# 7-jack-sensor-board.net
KiCad netlist of a schematic drawn in EAGLE
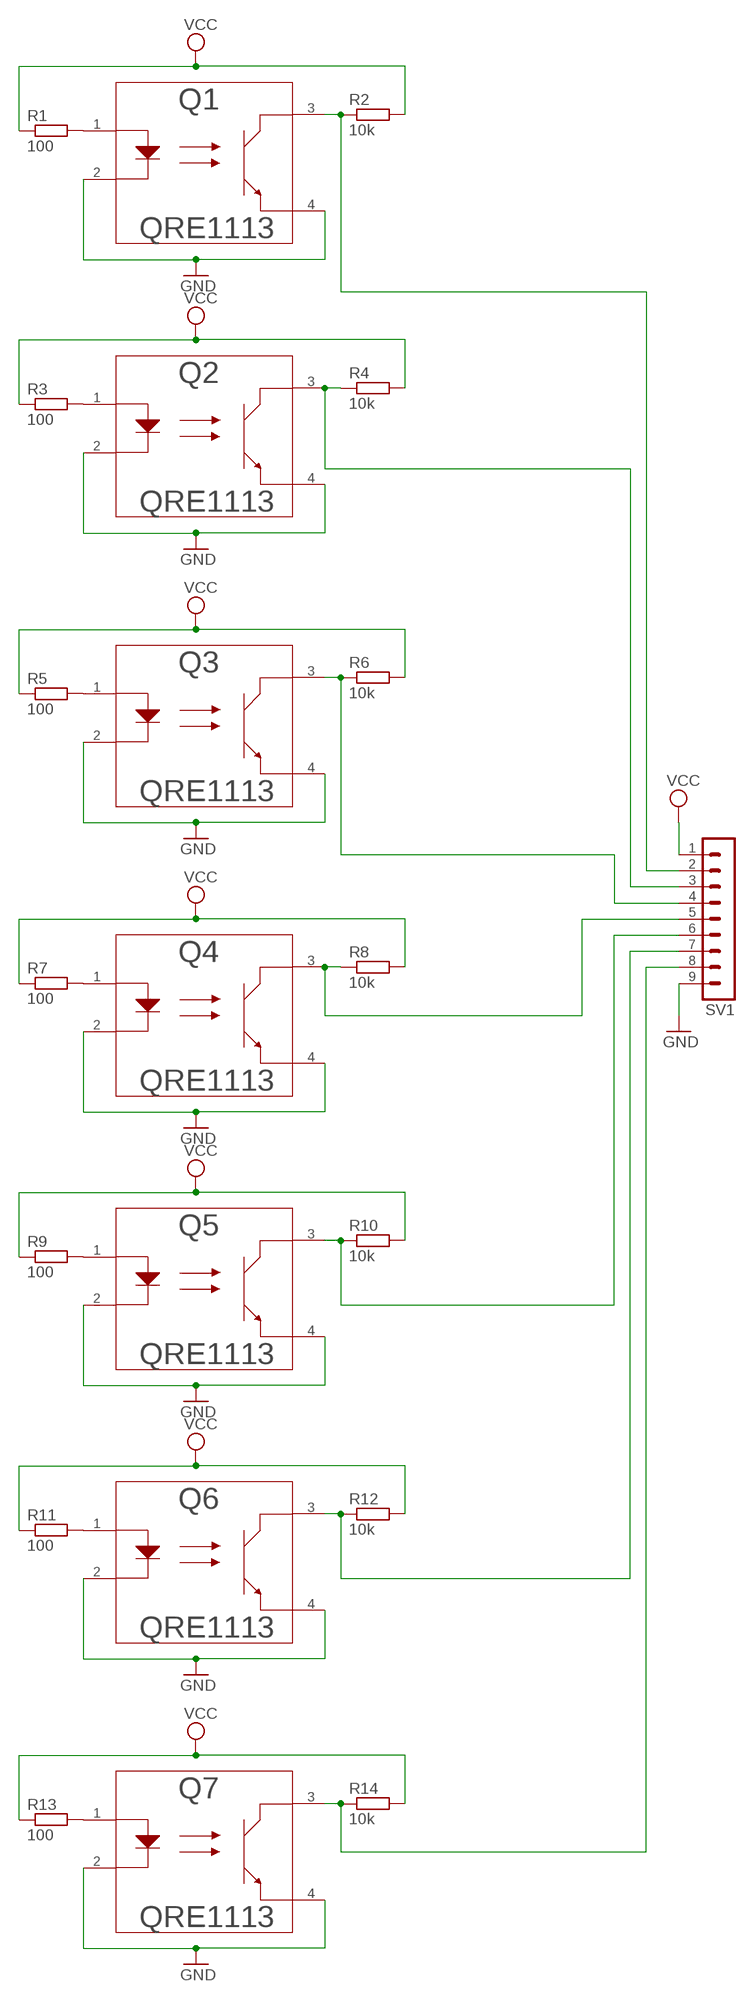
[diagram p0: schematic, sheet 1]

(export (version "E")
  (design (tool "Eeschema 10.0.6"))
  (components
    (comp (ref "Q1")
      (value "QRE1113")
      (footprint "eagle-import:DIP4_100AQ_ONS")
      (fields (field (name "COPYRIGHT") "Copyright (C) 2024 Ultra Librarian. All rights reserved."))
      (libsource (lib "eagle-import") (part "QRE1113"))
    )
    (comp (ref "Q2")
      (value "QRE1113")
      (footprint "eagle-import:DIP4_100AQ_ONS")
      (fields (field (name "COPYRIGHT") "Copyright (C) 2024 Ultra Librarian. All rights reserved."))
      (libsource (lib "eagle-import") (part "QRE1113"))
    )
    (comp (ref "Q3")
      (value "QRE1113")
      (footprint "eagle-import:DIP4_100AQ_ONS")
      (fields (field (name "COPYRIGHT") "Copyright (C) 2024 Ultra Librarian. All rights reserved."))
      (libsource (lib "eagle-import") (part "QRE1113"))
    )
    (comp (ref "Q4")
      (value "QRE1113")
      (footprint "eagle-import:DIP4_100AQ_ONS")
      (fields (field (name "COPYRIGHT") "Copyright (C) 2024 Ultra Librarian. All rights reserved."))
      (libsource (lib "eagle-import") (part "QRE1113"))
    )
    (comp (ref "Q5")
      (value "QRE1113")
      (footprint "eagle-import:DIP4_100AQ_ONS")
      (fields (field (name "COPYRIGHT") "Copyright (C) 2024 Ultra Librarian. All rights reserved."))
      (libsource (lib "eagle-import") (part "QRE1113"))
    )
    (comp (ref "Q6")
      (value "QRE1113")
      (footprint "eagle-import:DIP4_100AQ_ONS")
      (fields (field (name "COPYRIGHT") "Copyright (C) 2024 Ultra Librarian. All rights reserved."))
      (libsource (lib "eagle-import") (part "QRE1113"))
    )
    (comp (ref "Q7")
      (value "QRE1113")
      (footprint "eagle-import:DIP4_100AQ_ONS")
      (fields (field (name "COPYRIGHT") "Copyright (C) 2024 Ultra Librarian. All rights reserved."))
      (libsource (lib "eagle-import") (part "QRE1113"))
    )
    (comp (ref "R1")
      (value "100")
      (footprint "eagle-import:0207_10")
      (libsource (lib "eagle-import") (part "R-EU_0207/10"))
    )
    (comp (ref "R2")
      (value "10k")
      (footprint "eagle-import:0207_10")
      (libsource (lib "eagle-import") (part "R-EU_0207/10"))
    )
    (comp (ref "R3")
      (value "100")
      (footprint "eagle-import:0207_10")
      (libsource (lib "eagle-import") (part "R-EU_0207/10"))
    )
    (comp (ref "R4")
      (value "10k")
      (footprint "eagle-import:0207_10")
      (libsource (lib "eagle-import") (part "R-EU_0207/10"))
    )
    (comp (ref "R5")
      (value "100")
      (footprint "eagle-import:0207_10")
      (libsource (lib "eagle-import") (part "R-EU_0207/10"))
    )
    (comp (ref "R6")
      (value "10k")
      (footprint "eagle-import:0207_10")
      (libsource (lib "eagle-import") (part "R-EU_0207/10"))
    )
    (comp (ref "R7")
      (value "100")
      (footprint "eagle-import:0207_10")
      (libsource (lib "eagle-import") (part "R-EU_0207/10"))
    )
    (comp (ref "R8")
      (value "10k")
      (footprint "eagle-import:0207_10")
      (libsource (lib "eagle-import") (part "R-EU_0207/10"))
    )
    (comp (ref "R9")
      (value "100")
      (footprint "eagle-import:0207_10")
      (libsource (lib "eagle-import") (part "R-EU_0207/10"))
    )
    (comp (ref "R10")
      (value "10k")
      (footprint "eagle-import:0207_10")
      (libsource (lib "eagle-import") (part "R-EU_0207/10"))
    )
    (comp (ref "R11")
      (value "100")
      (footprint "eagle-import:0207_10")
      (libsource (lib "eagle-import") (part "R-EU_0207/10"))
    )
    (comp (ref "R12")
      (value "10k")
      (footprint "eagle-import:0207_10")
      (libsource (lib "eagle-import") (part "R-EU_0207/10"))
    )
    (comp (ref "R13")
      (value "100")
      (footprint "eagle-import:0207_10")
      (libsource (lib "eagle-import") (part "R-EU_0207/10"))
    )
    (comp (ref "R14")
      (value "10k")
      (footprint "eagle-import:0207_10")
      (libsource (lib "eagle-import") (part "R-EU_0207/10"))
    )
    (comp (ref "SV1")
      (value "MA09-1")
      (footprint "eagle-import:MA09-1")
      (libsource (lib "eagle-import") (part "MA09-1"))
    )
  )
  (nets
    (net (code "1") (name "GND") (class "Default")
      (node (ref "Q1") (pin "2") (pinfunction "2_2") (pintype "passive"))
      (node (ref "Q1") (pin "4") (pinfunction "4_4") (pintype "passive"))
      (node (ref "Q2") (pin "2") (pinfunction "2_2") (pintype "passive"))
      (node (ref "Q2") (pin "4") (pinfunction "4_4") (pintype "passive"))
      (node (ref "Q3") (pin "2") (pinfunction "2_2") (pintype "passive"))
      (node (ref "Q3") (pin "4") (pinfunction "4_4") (pintype "passive"))
      (node (ref "Q4") (pin "2") (pinfunction "2_2") (pintype "passive"))
      (node (ref "Q4") (pin "4") (pinfunction "4_4") (pintype "passive"))
      (node (ref "Q5") (pin "2") (pinfunction "2_2") (pintype "passive"))
      (node (ref "Q5") (pin "4") (pinfunction "4_4") (pintype "passive"))
      (node (ref "Q6") (pin "2") (pinfunction "2_2") (pintype "passive"))
      (node (ref "Q6") (pin "4") (pinfunction "4_4") (pintype "passive"))
      (node (ref "Q7") (pin "2") (pinfunction "2_2") (pintype "passive"))
      (node (ref "Q7") (pin "4") (pinfunction "4_4") (pintype "passive"))
      (node (ref "SV1") (pin "9") (pinfunction "9_9") (pintype "passive"))
    )
    (net (code "2") (name "Net-(Q1-Pad1)") (class "Default")
      (node (ref "Q1") (pin "1") (pinfunction "1_1") (pintype "passive"))
      (node (ref "R1") (pin "2") (pinfunction "2_2") (pintype "passive"))
    )
    (net (code "3") (name "Net-(Q1-Pad3)") (class "Default")
      (node (ref "Q1") (pin "3") (pinfunction "3_3") (pintype "passive"))
      (node (ref "R2") (pin "1") (pinfunction "1_1") (pintype "passive"))
      (node (ref "SV1") (pin "2") (pinfunction "2_2") (pintype "passive"))
    )
    (net (code "4") (name "Net-(Q2-Pad1)") (class "Default")
      (node (ref "Q2") (pin "1") (pinfunction "1_1") (pintype "passive"))
      (node (ref "R3") (pin "2") (pinfunction "2_2") (pintype "passive"))
    )
    (net (code "5") (name "Net-(Q2-Pad3)") (class "Default")
      (node (ref "Q2") (pin "3") (pinfunction "3_3") (pintype "passive"))
      (node (ref "R4") (pin "1") (pinfunction "1_1") (pintype "passive"))
      (node (ref "SV1") (pin "3") (pinfunction "3_3") (pintype "passive"))
    )
    (net (code "6") (name "Net-(Q3-Pad1)") (class "Default")
      (node (ref "Q3") (pin "1") (pinfunction "1_1") (pintype "passive"))
      (node (ref "R5") (pin "2") (pinfunction "2_2") (pintype "passive"))
    )
    (net (code "7") (name "Net-(Q3-Pad3)") (class "Default")
      (node (ref "Q3") (pin "3") (pinfunction "3_3") (pintype "passive"))
      (node (ref "R6") (pin "1") (pinfunction "1_1") (pintype "passive"))
      (node (ref "SV1") (pin "4") (pinfunction "4_4") (pintype "passive"))
    )
    (net (code "8") (name "Net-(Q4-Pad1)") (class "Default")
      (node (ref "Q4") (pin "1") (pinfunction "1_1") (pintype "passive"))
      (node (ref "R7") (pin "2") (pinfunction "2_2") (pintype "passive"))
    )
    (net (code "9") (name "Net-(Q4-Pad3)") (class "Default")
      (node (ref "Q4") (pin "3") (pinfunction "3_3") (pintype "passive"))
      (node (ref "R8") (pin "1") (pinfunction "1_1") (pintype "passive"))
      (node (ref "SV1") (pin "5") (pinfunction "5_5") (pintype "passive"))
    )
    (net (code "10") (name "Net-(Q5-Pad1)") (class "Default")
      (node (ref "Q5") (pin "1") (pinfunction "1_1") (pintype "passive"))
      (node (ref "R9") (pin "2") (pinfunction "2_2") (pintype "passive"))
    )
    (net (code "11") (name "Net-(Q5-Pad3)") (class "Default")
      (node (ref "Q5") (pin "3") (pinfunction "3_3") (pintype "passive"))
      (node (ref "R10") (pin "1") (pinfunction "1_1") (pintype "passive"))
      (node (ref "SV1") (pin "6") (pinfunction "6_6") (pintype "passive"))
    )
    (net (code "12") (name "Net-(Q6-Pad1)") (class "Default")
      (node (ref "Q6") (pin "1") (pinfunction "1_1") (pintype "passive"))
      (node (ref "R11") (pin "2") (pinfunction "2_2") (pintype "passive"))
    )
    (net (code "13") (name "Net-(Q6-Pad3)") (class "Default")
      (node (ref "Q6") (pin "3") (pinfunction "3_3") (pintype "passive"))
      (node (ref "R12") (pin "1") (pinfunction "1_1") (pintype "passive"))
      (node (ref "SV1") (pin "7") (pinfunction "7_7") (pintype "passive"))
    )
    (net (code "14") (name "Net-(Q7-Pad1)") (class "Default")
      (node (ref "Q7") (pin "1") (pinfunction "1_1") (pintype "passive"))
      (node (ref "R13") (pin "2") (pinfunction "2_2") (pintype "passive"))
    )
    (net (code "15") (name "Net-(Q7-Pad3)") (class "Default")
      (node (ref "Q7") (pin "3") (pinfunction "3_3") (pintype "passive"))
      (node (ref "R14") (pin "1") (pinfunction "1_1") (pintype "passive"))
      (node (ref "SV1") (pin "8") (pinfunction "8_8") (pintype "passive"))
    )
    (net (code "16") (name "VCC") (class "Default")
      (node (ref "R1") (pin "1") (pinfunction "1_1") (pintype "passive"))
      (node (ref "R10") (pin "2") (pinfunction "2_2") (pintype "passive"))
      (node (ref "R11") (pin "1") (pinfunction "1_1") (pintype "passive"))
      (node (ref "R12") (pin "2") (pinfunction "2_2") (pintype "passive"))
      (node (ref "R13") (pin "1") (pinfunction "1_1") (pintype "passive"))
      (node (ref "R14") (pin "2") (pinfunction "2_2") (pintype "passive"))
      (node (ref "R2") (pin "2") (pinfunction "2_2") (pintype "passive"))
      (node (ref "R3") (pin "1") (pinfunction "1_1") (pintype "passive"))
      (node (ref "R4") (pin "2") (pinfunction "2_2") (pintype "passive"))
      (node (ref "R5") (pin "1") (pinfunction "1_1") (pintype "passive"))
      (node (ref "R6") (pin "2") (pinfunction "2_2") (pintype "passive"))
      (node (ref "R7") (pin "1") (pinfunction "1_1") (pintype "passive"))
      (node (ref "R8") (pin "2") (pinfunction "2_2") (pintype "passive"))
      (node (ref "R9") (pin "1") (pinfunction "1_1") (pintype "passive"))
      (node (ref "SV1") (pin "1") (pinfunction "1_1") (pintype "passive"))
    )
  )
)
